# TMC2130.net
KiCad netlist of a schematic drawn in Altium Designer
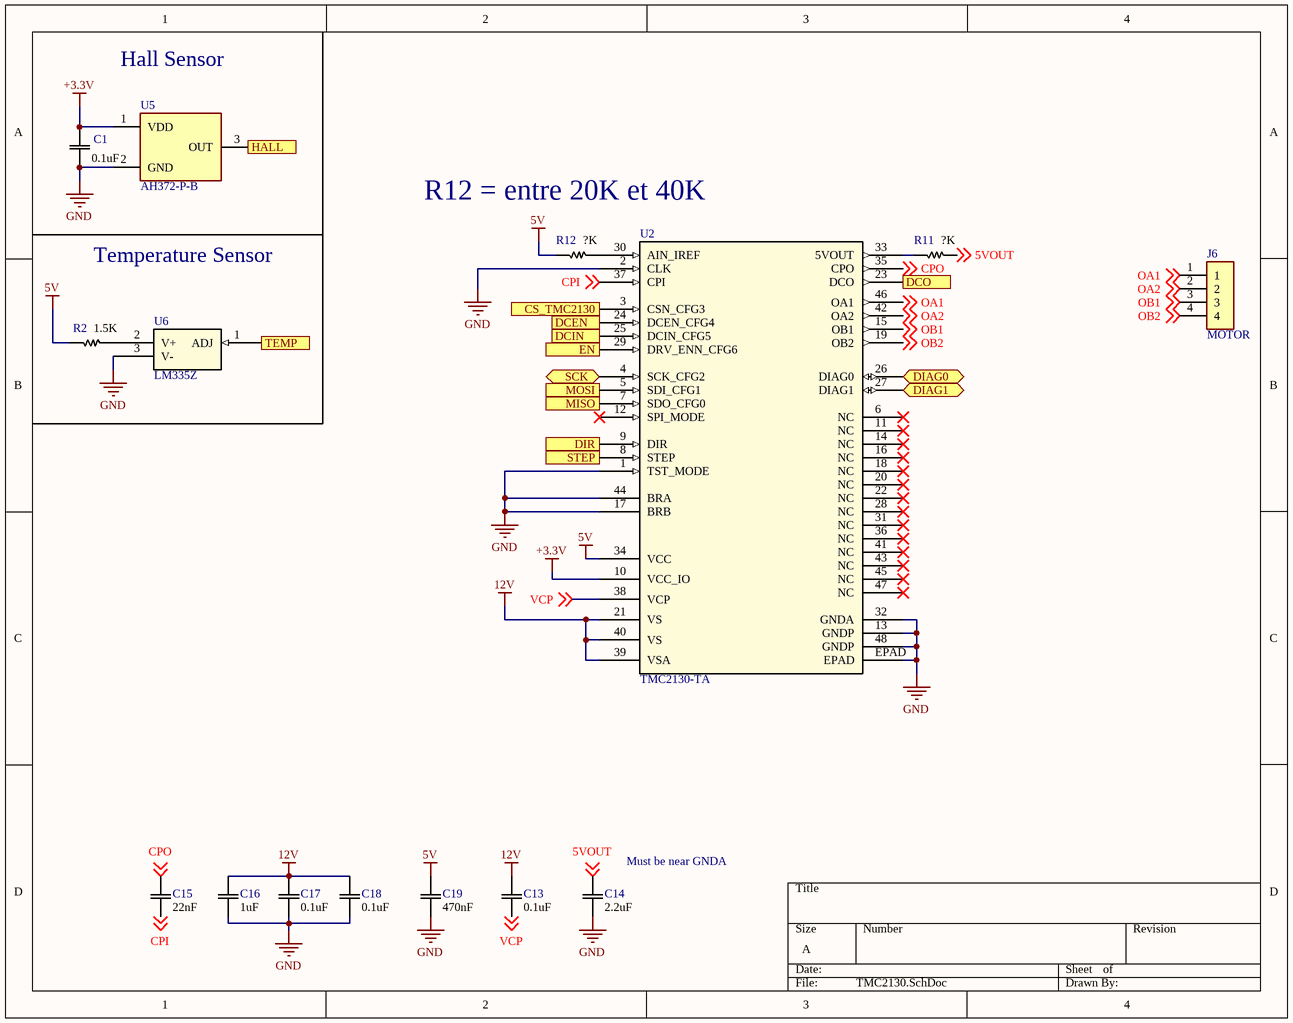
[diagram p0: TMC2130.SchDoc]

(export (version "E")
  (design (tool "Eeschema 10.0.6"))
  (components
    (comp (ref "C1")
      (value "0.1uF")
      (footprint "0603")
      (description "Capacitor SMD 1206")
      (fields
        (field (name "MANUFACTURER_PART_NUMBER") "12065A820JAT2A")
        (field (name "Comment") "Capacitor 1206")
        (field (name "COPYRIGHT") "Copyright (C) 2018 Accelerated Designs. All rights reserved")
      )
      (libsource (lib "Schematic_Emile") (part "Capacitor 1206"))
    )
    (comp (ref "C13")
      (value "0.1uF")
      (footprint "0603")
      (description "Capacitor SMD 1206")
      (fields
        (field (name "MANUFACTURER_PART_NUMBER") "12065A820JAT2A")
        (field (name "Comment") "Capacitor 1206")
        (field (name "COPYRIGHT") "Copyright (C) 2018 Accelerated Designs. All rights reserved")
      )
      (libsource (lib "Schematic_Emile") (part "Capacitor 1206"))
    )
    (comp (ref "C14")
      (value "2.2uF")
      (footprint "0603")
      (description "Capacitor SMD 1206")
      (fields
        (field (name "MANUFACTURER_PART_NUMBER") "12065A820JAT2A")
        (field (name "Comment") "Capacitor 1206")
        (field (name "COPYRIGHT") "Copyright (C) 2018 Accelerated Designs. All rights reserved")
      )
      (libsource (lib "Schematic_Emile") (part "Capacitor 1206"))
    )
    (comp (ref "C15")
      (value "22nF")
      (footprint "0603")
      (description "Capacitor SMD 1206")
      (fields
        (field (name "MANUFACTURER_PART_NUMBER") "12065A820JAT2A")
        (field (name "Comment") "Capacitor 1206")
        (field (name "COPYRIGHT") "Copyright (C) 2018 Accelerated Designs. All rights reserved")
      )
      (libsource (lib "Schematic_Emile") (part "Capacitor 1206"))
    )
    (comp (ref "C16")
      (value "1uF")
      (footprint "0603")
      (description "Capacitor SMD 1206")
      (fields
        (field (name "MANUFACTURER_PART_NUMBER") "12065A820JAT2A")
        (field (name "Comment") "Capacitor 1206")
        (field (name "COPYRIGHT") "Copyright (C) 2018 Accelerated Designs. All rights reserved")
      )
      (libsource (lib "Schematic_Emile") (part "Capacitor 1206"))
    )
    (comp (ref "C17")
      (value "0.1uF")
      (footprint "0603")
      (description "Capacitor SMD 1206")
      (fields
        (field (name "MANUFACTURER_PART_NUMBER") "12065A820JAT2A")
        (field (name "Comment") "Capacitor 1206")
        (field (name "COPYRIGHT") "Copyright (C) 2018 Accelerated Designs. All rights reserved")
      )
      (libsource (lib "Schematic_Emile") (part "Capacitor 1206"))
    )
    (comp (ref "C18")
      (value "0.1uF")
      (footprint "0603")
      (description "Capacitor SMD 1206")
      (fields
        (field (name "MANUFACTURER_PART_NUMBER") "12065A820JAT2A")
        (field (name "Comment") "Capacitor 1206")
        (field (name "COPYRIGHT") "Copyright (C) 2018 Accelerated Designs. All rights reserved")
      )
      (libsource (lib "Schematic_Emile") (part "Capacitor 1206"))
    )
    (comp (ref "C19")
      (value "470nF")
      (footprint "0603")
      (description "Capacitor SMD 1206")
      (fields
        (field (name "MANUFACTURER_PART_NUMBER") "12065A820JAT2A")
        (field (name "Comment") "Capacitor 1206")
        (field (name "COPYRIGHT") "Copyright (C) 2018 Accelerated Designs. All rights reserved")
      )
      (libsource (lib "Schematic_Emile") (part "Capacitor 1206"))
    )
    (comp (ref "J6")
      (value "MOTOR")
      (footprint "JST 4POS 2.5mm 90°")
      (description "Connector")
      (fields
        (field (name "MANUFACTURER_PART_NUMBER") "S4B-XH-A(LF)(SN)")
        (field (name "RS PART NUMBER") "8201589P")
      )
      (libsource (lib "Schematic_Emile") (part "JST 4POS"))
    )
    (comp (ref "R2")
      (value "1.5K")
      (footprint "0603")
      (description "Resistor 1206 SMD")
      (fields
        (field (name "MANUFACTURER_PART_NUMBER") "ERJ8CWFR024V")
        (field (name "Comment") "Resistor 1206")
        (field (name "COPYRIGHT") "Copyright (C) 2018 Accelerated Designs. All rights reserved")
      )
      (libsource (lib "Schematic_Emile") (part "Resistor 1206"))
    )
    (comp (ref "R11")
      (value "?K")
      (footprint "0603")
      (description "Resistor 1206 SMD")
      (fields
        (field (name "MANUFACTURER_PART_NUMBER") "ERJ8CWFR024V")
        (field (name "Comment") "Resistor 1206")
        (field (name "COPYRIGHT") "Copyright (C) 2018 Accelerated Designs. All rights reserved")
      )
      (libsource (lib "Schematic_Emile") (part "Resistor 1206"))
    )
    (comp (ref "R12")
      (value "?K")
      (footprint "0603")
      (description "Resistor 1206 SMD")
      (fields
        (field (name "MANUFACTURER_PART_NUMBER") "ERJ8CWFR024V")
        (field (name "Comment") "Resistor 1206")
        (field (name "COPYRIGHT") "Copyright (C) 2018 Accelerated Designs. All rights reserved")
      )
      (libsource (lib "Schematic_Emile") (part "Resistor 1206"))
    )
    (comp (ref "U2")
      (value "TMC2130-TA")
      (footprint "eTQFP48_9x9")
      (description "Motor Driver TMC2130")
      (fields (field (name "COPYRIGHT") "Copyright (C) 2016 Accelerated Designs. All rights reserved"))
      (libsource (lib "Schematic_Emile") (part "TMC2130-TA"))
    )
    (comp (ref "U5")
      (value "AH372-P-B")
      (footprint "SamacSys:AH372PB")
      (description "Hall Sensor")
      (fields (field (name "MOUSER PART NUMBER") "621-AH372-P-B") (field (name "RS PART NUMBER") "1333361P"))
      (libsource (lib "Schematic_Emile") (part "AH372-P-B"))
    )
    (comp (ref "U6")
      (value "LM335Z")
      (footprint "TO92")
      (description "Temperature Sensor")
      (fields (field (name "COPYRIGHT") "Copyright (C) 2018 Accelerated Designs. All rights reserved"))
      (libsource (lib "Schematic_Emile") (part "LM335Z"))
    )
  )
  (nets
    (net (code "1") (name "+3.3V") (class "Default")
      (node (ref "C1") (pin "2") (pinfunction "2_2") (pintype "passive"))
      (node (ref "U2") (pin "10") (pinfunction "VCC_IO_10") (pintype "power_in"))
      (node (ref "U5") (pin "1") (pinfunction "VDD_1") (pintype "passive"))
    )
    (net (code "2") (name "/CS_TMC2130") (class "Default")
      (node (ref "U2") (pin "3") (pinfunction "CSN_CFG3_3") (pintype "input"))
    )
    (net (code "3") (name "/DCEN") (class "Default")
      (node (ref "U2") (pin "24") (pinfunction "DCEN_CFG4_24") (pintype "input"))
    )
    (net (code "4") (name "/DCIN") (class "Default")
      (node (ref "U2") (pin "25") (pinfunction "DCIN_CFG5_25") (pintype "input"))
    )
    (net (code "5") (name "/DCO") (class "Default")
      (node (ref "U2") (pin "23") (pinfunction "DCO_23") (pintype "output"))
    )
    (net (code "6") (name "/DIAG0") (class "Default")
      (node (ref "U2") (pin "26") (pinfunction "DIAG0_26") (pintype "bidirectional"))
    )
    (net (code "7") (name "/DIAG1") (class "Default")
      (node (ref "U2") (pin "27") (pinfunction "DIAG1_27") (pintype "bidirectional"))
    )
    (net (code "8") (name "/DIR") (class "Default")
      (node (ref "U2") (pin "9") (pinfunction "DIR_9") (pintype "input"))
    )
    (net (code "9") (name "/EN") (class "Default")
      (node (ref "U2") (pin "29") (pinfunction "DRV_ENN_CFG6_29") (pintype "input"))
    )
    (net (code "10") (name "/HALL") (class "Default")
      (node (ref "U5") (pin "3") (pinfunction "OUT_3") (pintype "passive"))
    )
    (net (code "11") (name "/MISO") (class "Default")
      (node (ref "U2") (pin "7") (pinfunction "SDO_CFG0_7") (pintype "input"))
    )
    (net (code "12") (name "/MOSI") (class "Default")
      (node (ref "U2") (pin "5") (pinfunction "SDI_CFG1_5") (pintype "input"))
    )
    (net (code "13") (name "/SCK") (class "Default")
      (node (ref "U2") (pin "4") (pinfunction "SCK_CFG2_4") (pintype "input"))
    )
    (net (code "14") (name "/STEP") (class "Default")
      (node (ref "U2") (pin "8") (pinfunction "STEP_8") (pintype "input"))
    )
    (net (code "15") (name "/TEMP") (class "Default")
      (node (ref "U6") (pin "1") (pinfunction "ADJ_1") (pintype "input"))
    )
    (net (code "16") (name "5V") (class "Default")
      (node (ref "C19") (pin "2") (pinfunction "2_2") (pintype "passive"))
      (node (ref "R12") (pin "1") (pinfunction "1_1") (pintype "passive"))
      (node (ref "R2") (pin "1") (pinfunction "1_1") (pintype "passive"))
      (node (ref "U2") (pin "34") (pinfunction "VCC_34") (pintype "power_in"))
    )
    (net (code "17") (name "5VOUT") (class "Default")
      (node (ref "C14") (pin "2") (pinfunction "2_2") (pintype "passive"))
      (node (ref "R11") (pin "2") (pinfunction "2_2") (pintype "passive"))
    )
    (net (code "18") (name "12V") (class "Default")
      (node (ref "C13") (pin "2") (pinfunction "2_2") (pintype "passive"))
      (node (ref "C16") (pin "2") (pinfunction "2_2") (pintype "passive"))
      (node (ref "C17") (pin "2") (pinfunction "2_2") (pintype "passive"))
      (node (ref "C18") (pin "2") (pinfunction "2_2") (pintype "passive"))
      (node (ref "U2") (pin "21") (pinfunction "VS_21") (pintype "power_in"))
      (node (ref "U2") (pin "39") (pinfunction "VSA_39") (pintype "power_in"))
      (node (ref "U2") (pin "40") (pinfunction "VS_40") (pintype "power_in"))
    )
    (net (code "19") (name "CPI") (class "Default")
      (node (ref "C15") (pin "1") (pinfunction "1_1") (pintype "passive"))
      (node (ref "U2") (pin "37") (pinfunction "CPI_37") (pintype "input"))
    )
    (net (code "20") (name "CPO") (class "Default")
      (node (ref "C15") (pin "2") (pinfunction "2_2") (pintype "passive"))
      (node (ref "U2") (pin "35") (pinfunction "CPO_35") (pintype "output"))
    )
    (net (code "21") (name "GND") (class "Default")
      (node (ref "C1") (pin "1") (pinfunction "1_1") (pintype "passive"))
      (node (ref "C14") (pin "1") (pinfunction "1_1") (pintype "passive"))
      (node (ref "C16") (pin "1") (pinfunction "1_1") (pintype "passive"))
      (node (ref "C17") (pin "1") (pinfunction "1_1") (pintype "passive"))
      (node (ref "C18") (pin "1") (pinfunction "1_1") (pintype "passive"))
      (node (ref "C19") (pin "1") (pinfunction "1_1") (pintype "passive"))
      (node (ref "U2") (pin "1") (pinfunction "TST_MODE_1") (pintype "input"))
      (node (ref "U2") (pin "13") (pinfunction "GNDP_13") (pintype "power_in"))
      (node (ref "U2") (pin "17") (pinfunction "BRB_17") (pintype "passive"))
      (node (ref "U2") (pin "2") (pinfunction "CLK_2") (pintype "input"))
      (node (ref "U2") (pin "32") (pinfunction "GNDA_32") (pintype "power_in"))
      (node (ref "U2") (pin "44") (pinfunction "BRA_44") (pintype "passive"))
      (node (ref "U2") (pin "48") (pinfunction "GNDP_48") (pintype "power_in"))
      (node (ref "U2") (pin "EPAD") (pinfunction "EPAD_EPAD") (pintype "passive"))
      (node (ref "U5") (pin "2") (pinfunction "GND_2") (pintype "passive"))
      (node (ref "U6") (pin "3") (pinfunction "V-_3") (pintype "power_in"))
    )
    (net (code "22") (name "Net-(U2-5VOUT)") (class "Default")
      (node (ref "R11") (pin "1") (pinfunction "1_1") (pintype "passive"))
      (node (ref "U2") (pin "33") (pinfunction "5VOUT_33") (pintype "output"))
    )
    (net (code "23") (name "Net-(U2-AIN_IREF)") (class "Default")
      (node (ref "R12") (pin "2") (pinfunction "2_2") (pintype "passive"))
      (node (ref "U2") (pin "30") (pinfunction "AIN_IREF_30") (pintype "input"))
    )
    (net (code "24") (name "Net-(U6-V+)") (class "Default")
      (node (ref "R2") (pin "2") (pinfunction "2_2") (pintype "passive"))
      (node (ref "U6") (pin "2") (pinfunction "V+_2") (pintype "power_in"))
    )
    (net (code "25") (name "OA1") (class "Default")
      (node (ref "J6") (pin "1") (pinfunction "1_1") (pintype "passive"))
      (node (ref "U2") (pin "46") (pinfunction "OA1_46") (pintype "output"))
    )
    (net (code "26") (name "OA2") (class "Default")
      (node (ref "J6") (pin "2") (pinfunction "2_2") (pintype "passive"))
      (node (ref "U2") (pin "42") (pinfunction "OA2_42") (pintype "output"))
    )
    (net (code "27") (name "OB1") (class "Default")
      (node (ref "J6") (pin "3") (pinfunction "3_3") (pintype "passive"))
      (node (ref "U2") (pin "15") (pinfunction "OB1_15") (pintype "output"))
    )
    (net (code "28") (name "OB2") (class "Default")
      (node (ref "J6") (pin "4") (pinfunction "4_4") (pintype "passive"))
      (node (ref "U2") (pin "19") (pinfunction "OB2_19") (pintype "output"))
    )
    (net (code "29") (name "VCP") (class "Default")
      (node (ref "C13") (pin "1") (pinfunction "1_1") (pintype "passive"))
      (node (ref "U2") (pin "38") (pinfunction "VCP_38") (pintype "power_in"))
    )
    (net (code "30") (name "unconnected-(U2-NC-Pad6)") (class "Default")
      (node (ref "U2") (pin "6") (pinfunction "NC_6") (pintype "passive+no_connect"))
    )
    (net (code "31") (name "unconnected-(U2-NC-Pad11)") (class "Default")
      (node (ref "U2") (pin "11") (pinfunction "NC_11") (pintype "passive+no_connect"))
    )
    (net (code "32") (name "unconnected-(U2-NC-Pad14)") (class "Default")
      (node (ref "U2") (pin "14") (pinfunction "NC_14") (pintype "passive+no_connect"))
    )
    (net (code "33") (name "unconnected-(U2-NC-Pad16)") (class "Default")
      (node (ref "U2") (pin "16") (pinfunction "NC_16") (pintype "passive+no_connect"))
    )
    (net (code "34") (name "unconnected-(U2-NC-Pad18)") (class "Default")
      (node (ref "U2") (pin "18") (pinfunction "NC_18") (pintype "passive+no_connect"))
    )
    (net (code "35") (name "unconnected-(U2-NC-Pad20)") (class "Default")
      (node (ref "U2") (pin "20") (pinfunction "NC_20") (pintype "passive+no_connect"))
    )
    (net (code "36") (name "unconnected-(U2-NC-Pad22)") (class "Default")
      (node (ref "U2") (pin "22") (pinfunction "NC_22") (pintype "passive+no_connect"))
    )
    (net (code "37") (name "unconnected-(U2-NC-Pad28)") (class "Default")
      (node (ref "U2") (pin "28") (pinfunction "NC_28") (pintype "passive+no_connect"))
    )
    (net (code "38") (name "unconnected-(U2-NC-Pad31)") (class "Default")
      (node (ref "U2") (pin "31") (pinfunction "NC_31") (pintype "passive+no_connect"))
    )
    (net (code "39") (name "unconnected-(U2-NC-Pad36)") (class "Default")
      (node (ref "U2") (pin "36") (pinfunction "NC_36") (pintype "passive+no_connect"))
    )
    (net (code "40") (name "unconnected-(U2-NC-Pad41)") (class "Default")
      (node (ref "U2") (pin "41") (pinfunction "NC_41") (pintype "passive+no_connect"))
    )
    (net (code "41") (name "unconnected-(U2-NC-Pad43)") (class "Default")
      (node (ref "U2") (pin "43") (pinfunction "NC_43") (pintype "passive+no_connect"))
    )
    (net (code "42") (name "unconnected-(U2-NC-Pad45)") (class "Default")
      (node (ref "U2") (pin "45") (pinfunction "NC_45") (pintype "passive+no_connect"))
    )
    (net (code "43") (name "unconnected-(U2-NC-Pad47)") (class "Default")
      (node (ref "U2") (pin "47") (pinfunction "NC_47") (pintype "passive+no_connect"))
    )
    (net (code "44") (name "unconnected-(U2-SPI_MODE-Pad12)") (class "Default")
      (node (ref "U2") (pin "12") (pinfunction "SPI_MODE_12") (pintype "input+no_connect"))
    )
  )
)
